# MicroSD-.net
KiCad netlist of a schematic drawn in Altium Designer
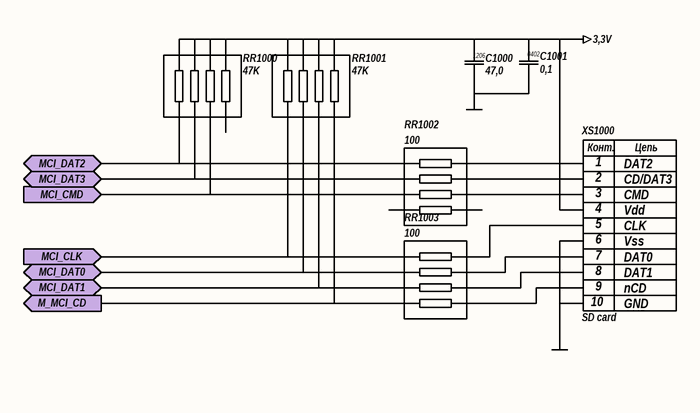
[diagram p0: MicroSD-карта.SchDoc]

(export (version "E")
  (design (tool "Eeschema 10.0.6"))
  (components
    (comp (ref "C1000")
      (value "47,0")
      (footprint "CAP1206")
      (description "Конденсатор чип")
      (libsource (lib "EwgPassive") (part "CAP_1206"))
    )
    (comp (ref "C1001")
      (value "0,1")
      (footprint "CAP0402")
      (description "Конденсатор чип")
      (libsource (lib "EwgPassive") (part "CAP_0402"))
    )
    (comp (ref "RR1000")
      (value "47K")
      (footprint "CAY16")
      (description "Сборка резисторная")
      (libsource (lib "EwgPassive") (part "RESASM_CAY16"))
    )
    (comp (ref "RR1001")
      (value "47K")
      (footprint "CAY16")
      (description "Сборка резисторная")
      (libsource (lib "EwgPassive") (part "RESASM_CAY16"))
    )
    (comp (ref "RR1002")
      (value "100")
      (footprint "CAY16")
      (description "Сборка резисторная")
      (libsource (lib "EwgPassive") (part "RESASM_CAY16"))
    )
    (comp (ref "RR1003")
      (value "100")
      (footprint "CAY16")
      (description "Сборка резисторная")
      (libsource (lib "EwgPassive") (part "RESASM_CAY16"))
    )
    (comp (ref "XS1000")
      (value "SD card")
      (footprint "112J-TDAR-R-SDCARD")
      (description "Слот MMC")
      (libsource (lib "EwgConnectors") (part "112J-TDAR-R-SDCARD"))
    )
  )
  (nets
    (net (code "1") (name "/MCI_CLK") (class "Default")
      (node (ref "RR1001") (pin "4") (pinfunction "4_4") (pintype "passive"))
      (node (ref "RR1003") (pin "1") (pinfunction "1_1") (pintype "passive"))
    )
    (net (code "2") (name "/MCI_CMD") (class "Default")
      (node (ref "RR1000") (pin "2") (pinfunction "2_2") (pintype "passive"))
      (node (ref "RR1002") (pin "3") (pinfunction "3_3") (pintype "passive"))
    )
    (net (code "3") (name "/MCI_DAT0") (class "Default")
      (node (ref "RR1001") (pin "3") (pinfunction "3_3") (pintype "passive"))
      (node (ref "RR1003") (pin "2") (pinfunction "2_2") (pintype "passive"))
    )
    (net (code "4") (name "/MCI_DAT1") (class "Default")
      (node (ref "RR1001") (pin "2") (pinfunction "2_2") (pintype "passive"))
      (node (ref "RR1003") (pin "3") (pinfunction "3_3") (pintype "passive"))
    )
    (net (code "5") (name "/MCI_DAT2") (class "Default")
      (node (ref "RR1000") (pin "4") (pinfunction "4_4") (pintype "passive"))
      (node (ref "RR1002") (pin "1") (pinfunction "1_1") (pintype "passive"))
    )
    (net (code "6") (name "/MCI_DAT3") (class "Default")
      (node (ref "RR1000") (pin "3") (pinfunction "3_3") (pintype "passive"))
      (node (ref "RR1002") (pin "2") (pinfunction "2_2") (pintype "passive"))
    )
    (net (code "7") (name "/M_MCI_CD") (class "Default")
      (node (ref "RR1001") (pin "1") (pinfunction "1_1") (pintype "passive"))
      (node (ref "RR1003") (pin "4") (pinfunction "4_4") (pintype "passive"))
    )
    (net (code "8") (name "3,3V") (class "Default")
      (node (ref "C1000") (pin "1") (pintype "passive"))
      (node (ref "C1001") (pin "1") (pintype "passive"))
      (node (ref "RR1000") (pin "5") (pinfunction "5_5") (pintype "passive"))
      (node (ref "RR1000") (pin "6") (pinfunction "6_6") (pintype "passive"))
      (node (ref "RR1000") (pin "7") (pinfunction "7_7") (pintype "passive"))
      (node (ref "RR1000") (pin "8") (pinfunction "8_8") (pintype "passive"))
      (node (ref "RR1001") (pin "5") (pinfunction "5_5") (pintype "passive"))
      (node (ref "RR1001") (pin "6") (pinfunction "6_6") (pintype "passive"))
      (node (ref "RR1001") (pin "7") (pinfunction "7_7") (pintype "passive"))
      (node (ref "RR1001") (pin "8") (pinfunction "8_8") (pintype "passive"))
      (node (ref "XS1000") (pin "4") (pinfunction "Vdd_4") (pintype "passive"))
    )
    (net (code "9") (name "GND") (class "Default")
      (node (ref "C1000") (pin "2") (pintype "passive"))
      (node (ref "C1001") (pin "2") (pintype "passive"))
      (node (ref "XS1000") (pin "10") (pinfunction "GND_10") (pintype "passive"))
      (node (ref "XS1000") (pin "6") (pinfunction "Vss_6") (pintype "passive"))
    )
    (net (code "10") (name "Net-(XS1000-CD{slash}DAT3)") (class "Default")
      (node (ref "RR1002") (pin "7") (pinfunction "7_7") (pintype "passive"))
      (node (ref "XS1000") (pin "2") (pinfunction "CD/DAT3_2") (pintype "passive"))
    )
    (net (code "11") (name "Net-(XS1000-CLK)") (class "Default")
      (node (ref "RR1003") (pin "8") (pinfunction "8_8") (pintype "passive"))
      (node (ref "XS1000") (pin "5") (pinfunction "CLK_5") (pintype "passive"))
    )
    (net (code "12") (name "Net-(XS1000-CMD)") (class "Default")
      (node (ref "RR1002") (pin "6") (pinfunction "6_6") (pintype "passive"))
      (node (ref "XS1000") (pin "3") (pinfunction "CMD_3") (pintype "passive"))
    )
    (net (code "13") (name "Net-(XS1000-DAT0)") (class "Default")
      (node (ref "RR1003") (pin "7") (pinfunction "7_7") (pintype "passive"))
      (node (ref "XS1000") (pin "7") (pinfunction "DAT0_7") (pintype "passive"))
    )
    (net (code "14") (name "Net-(XS1000-DAT1)") (class "Default")
      (node (ref "RR1003") (pin "6") (pinfunction "6_6") (pintype "passive"))
      (node (ref "XS1000") (pin "8") (pinfunction "DAT1_8") (pintype "passive"))
    )
    (net (code "15") (name "Net-(XS1000-DAT2)") (class "Default")
      (node (ref "RR1002") (pin "8") (pinfunction "8_8") (pintype "passive"))
      (node (ref "XS1000") (pin "1") (pinfunction "DAT2_1") (pintype "passive"))
    )
    (net (code "16") (name "Net-(XS1000-nCD)") (class "Default")
      (node (ref "RR1003") (pin "5") (pinfunction "5_5") (pintype "passive"))
      (node (ref "XS1000") (pin "9") (pinfunction "nCD_9") (pintype "passive"))
    )
    (net (code "17") (name "unconnected-(RR1000-Pad1)") (class "Default")
      (node (ref "RR1000") (pin "1") (pinfunction "1_1") (pintype "passive"))
    )
    (net (code "18") (name "unconnected-(RR1002-Pad4)") (class "Default")
      (node (ref "RR1002") (pin "4") (pinfunction "4_4") (pintype "passive"))
    )
    (net (code "19") (name "unconnected-(RR1002-Pad5)") (class "Default")
      (node (ref "RR1002") (pin "5") (pinfunction "5_5") (pintype "passive"))
    )
  )
)
